# main.net
KiCad netlist of a schematic drawn in EAGLE
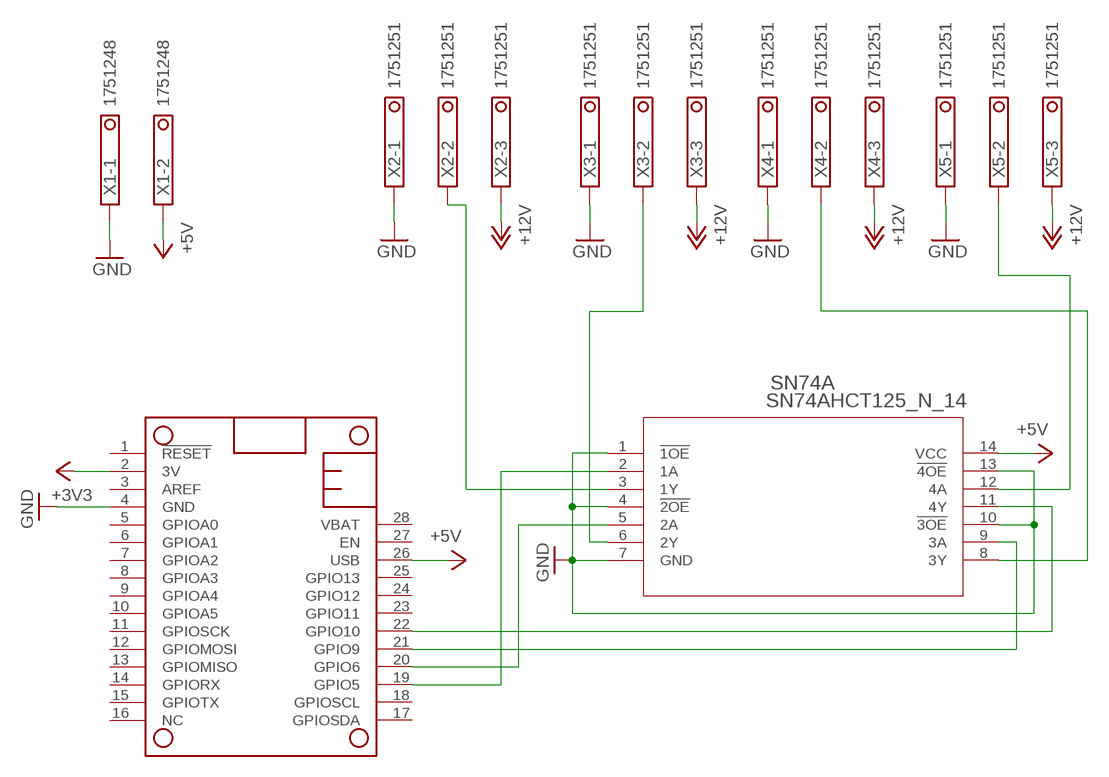
[diagram p0: schematic, sheet 1]

(export (version "E")
  (design (tool "Eeschema 10.0.6"))
  (components
    (comp (ref "MS1")
      (value "FEATHERWING_NODIM")
      (footprint "eagle-import:FEATHERWING_DIM")
      (libsource (lib "eagle-import") (part "FEATHERWING_NODIM"))
    )
    (comp (ref "SN74A")
      (value "SN74AHCT125_N_14")
      (footprint "eagle-import:N14")
      (fields (field (name "MANUFACTURER_PART_NUMBER") "sn74ahct125_n_14"))
      (libsource (lib "eagle-import") (part "SN74AHCT125_N_14"))
    )
    (comp (ref "X1")
      (value "1751248")
      (footprint "eagle-import:1751248")
      (libsource (lib "eagle-import") (part "1751248"))
    )
    (comp (ref "X2")
      (value "1751251")
      (footprint "eagle-import:1751251")
      (libsource (lib "eagle-import") (part "1751251"))
    )
    (comp (ref "X3")
      (value "1751251")
      (footprint "eagle-import:1751251")
      (libsource (lib "eagle-import") (part "1751251"))
    )
    (comp (ref "X4")
      (value "1751251")
      (footprint "eagle-import:1751251")
      (libsource (lib "eagle-import") (part "1751251"))
    )
    (comp (ref "X5")
      (value "1751251")
      (footprint "eagle-import:1751251")
      (libsource (lib "eagle-import") (part "1751251"))
    )
  )
  (nets
    (net (code "1") (name "+3V3") (class "Default")
      (node (ref "MS1") (pin "2") (pinfunction "3V_2") (pintype "power_in"))
    )
    (net (code "2") (name "+5V") (class "Default")
      (node (ref "MS1") (pin "26") (pinfunction "USB_26") (pintype "power_in"))
      (node (ref "SN74A") (pin "14") (pinfunction "VCC_14") (pintype "power_in"))
      (node (ref "X1") (pin "2") (pinfunction "K_2") (pintype "passive"))
    )
    (net (code "3") (name "+12V") (class "Default")
      (node (ref "X2") (pin "3") (pinfunction "K_3") (pintype "passive"))
      (node (ref "X3") (pin "3") (pinfunction "K_3") (pintype "passive"))
      (node (ref "X4") (pin "3") (pinfunction "K_3") (pintype "passive"))
      (node (ref "X5") (pin "3") (pinfunction "K_3") (pintype "passive"))
    )
    (net (code "4") (name "/VBAT") (class "Default")
      (node (ref "MS1") (pin "28") (pinfunction "VBAT_28") (pintype "power_in"))
    )
    (net (code "5") (name "GND") (class "Default")
      (node (ref "MS1") (pin "4") (pinfunction "GND_4") (pintype "power_in"))
      (node (ref "SN74A") (pin "1") (pinfunction "~{1OE}_1") (pintype "input"))
      (node (ref "SN74A") (pin "10") (pinfunction "~{3OE}_10") (pintype "input"))
      (node (ref "SN74A") (pin "13") (pinfunction "~{4OE}_13") (pintype "input"))
      (node (ref "SN74A") (pin "4") (pinfunction "~{2OE}_4") (pintype "input"))
      (node (ref "SN74A") (pin "7") (pinfunction "GND_7") (pintype "power_in"))
      (node (ref "X1") (pin "1") (pinfunction "K_1") (pintype "passive"))
      (node (ref "X2") (pin "1") (pinfunction "K_1") (pintype "passive"))
      (node (ref "X3") (pin "1") (pinfunction "K_1") (pintype "passive"))
      (node (ref "X4") (pin "1") (pinfunction "K_1") (pintype "passive"))
      (node (ref "X5") (pin "1") (pinfunction "K_1") (pintype "passive"))
    )
    (net (code "6") (name "Net-(MS1-GPIO5)") (class "Default")
      (node (ref "MS1") (pin "19") (pinfunction "GPIO5_19") (pintype "bidirectional"))
      (node (ref "SN74A") (pin "2") (pinfunction "1A_2") (pintype "input"))
    )
    (net (code "7") (name "Net-(MS1-GPIO6)") (class "Default")
      (node (ref "MS1") (pin "20") (pinfunction "GPIO6_20") (pintype "bidirectional"))
      (node (ref "SN74A") (pin "5") (pinfunction "2A_5") (pintype "input"))
    )
    (net (code "8") (name "Net-(MS1-GPIO9)") (class "Default")
      (node (ref "MS1") (pin "21") (pinfunction "GPIO9_21") (pintype "bidirectional"))
      (node (ref "SN74A") (pin "9") (pinfunction "3A_9") (pintype "input"))
    )
    (net (code "9") (name "Net-(MS1-GPIO10)") (class "Default")
      (node (ref "MS1") (pin "22") (pinfunction "GPIO10_22") (pintype "bidirectional"))
      (node (ref "SN74A") (pin "11") (pinfunction "4Y_11") (pintype "passive"))
    )
    (net (code "10") (name "Net-(SN74A-1Y)") (class "Default")
      (node (ref "SN74A") (pin "3") (pinfunction "1Y_3") (pintype "passive"))
      (node (ref "X2") (pin "2") (pinfunction "K_2") (pintype "passive"))
    )
    (net (code "11") (name "Net-(SN74A-2Y)") (class "Default")
      (node (ref "SN74A") (pin "6") (pinfunction "2Y_6") (pintype "passive"))
      (node (ref "X3") (pin "2") (pinfunction "K_2") (pintype "passive"))
    )
    (net (code "12") (name "Net-(SN74A-3Y)") (class "Default")
      (node (ref "SN74A") (pin "8") (pinfunction "3Y_8") (pintype "passive"))
      (node (ref "X4") (pin "2") (pinfunction "K_2") (pintype "passive"))
    )
    (net (code "13") (name "Net-(SN74A-4A)") (class "Default")
      (node (ref "SN74A") (pin "12") (pinfunction "4A_12") (pintype "input"))
      (node (ref "X5") (pin "2") (pinfunction "K_2") (pintype "passive"))
    )
    (net (code "14") (name "unconnected-(MS1-AREF-Pad3)") (class "Default")
      (node (ref "MS1") (pin "3") (pinfunction "AREF_3") (pintype "passive"))
    )
    (net (code "15") (name "unconnected-(MS1-EN-Pad27)") (class "Default")
      (node (ref "MS1") (pin "27") (pinfunction "EN_27") (pintype "passive"))
    )
    (net (code "16") (name "unconnected-(MS1-GPIO11-Pad23)") (class "Default")
      (node (ref "MS1") (pin "23") (pinfunction "GPIO11_23") (pintype "bidirectional"))
    )
    (net (code "17") (name "unconnected-(MS1-GPIO12-Pad24)") (class "Default")
      (node (ref "MS1") (pin "24") (pinfunction "GPIO12_24") (pintype "bidirectional"))
    )
    (net (code "18") (name "unconnected-(MS1-GPIO13-Pad25)") (class "Default")
      (node (ref "MS1") (pin "25") (pinfunction "GPIO13_25") (pintype "bidirectional"))
    )
    (net (code "19") (name "unconnected-(MS1-GPIOA0-Pad5)") (class "Default")
      (node (ref "MS1") (pin "5") (pinfunction "GPIOA0_5") (pintype "bidirectional"))
    )
    (net (code "20") (name "unconnected-(MS1-GPIOA1-Pad6)") (class "Default")
      (node (ref "MS1") (pin "6") (pinfunction "GPIOA1_6") (pintype "bidirectional"))
    )
    (net (code "21") (name "unconnected-(MS1-GPIOA2-Pad7)") (class "Default")
      (node (ref "MS1") (pin "7") (pinfunction "GPIOA2_7") (pintype "bidirectional"))
    )
    (net (code "22") (name "unconnected-(MS1-GPIOA3-Pad8)") (class "Default")
      (node (ref "MS1") (pin "8") (pinfunction "GPIOA3_8") (pintype "bidirectional"))
    )
    (net (code "23") (name "unconnected-(MS1-GPIOA4-Pad9)") (class "Default")
      (node (ref "MS1") (pin "9") (pinfunction "GPIOA4_9") (pintype "bidirectional"))
    )
    (net (code "24") (name "unconnected-(MS1-GPIOA5-Pad10)") (class "Default")
      (node (ref "MS1") (pin "10") (pinfunction "GPIOA5_10") (pintype "bidirectional"))
    )
    (net (code "25") (name "unconnected-(MS1-GPIOMISO-Pad13)") (class "Default")
      (node (ref "MS1") (pin "13") (pinfunction "GPIOMISO_13") (pintype "bidirectional"))
    )
    (net (code "26") (name "unconnected-(MS1-GPIOMOSI-Pad12)") (class "Default")
      (node (ref "MS1") (pin "12") (pinfunction "GPIOMOSI_12") (pintype "bidirectional"))
    )
    (net (code "27") (name "unconnected-(MS1-GPIORX-Pad14)") (class "Default")
      (node (ref "MS1") (pin "14") (pinfunction "GPIORX_14") (pintype "bidirectional"))
    )
    (net (code "28") (name "unconnected-(MS1-GPIOSCK-Pad11)") (class "Default")
      (node (ref "MS1") (pin "11") (pinfunction "GPIOSCK_11") (pintype "bidirectional"))
    )
    (net (code "29") (name "unconnected-(MS1-GPIOSCL-Pad18)") (class "Default")
      (node (ref "MS1") (pin "18") (pinfunction "GPIOSCL_18") (pintype "bidirectional"))
    )
    (net (code "30") (name "unconnected-(MS1-GPIOSDA-Pad17)") (class "Default")
      (node (ref "MS1") (pin "17") (pinfunction "GPIOSDA_17") (pintype "bidirectional"))
    )
    (net (code "31") (name "unconnected-(MS1-GPIOTX-Pad15)") (class "Default")
      (node (ref "MS1") (pin "15") (pinfunction "GPIOTX_15") (pintype "bidirectional"))
    )
    (net (code "32") (name "unconnected-(MS1-NC-Pad16)") (class "Default")
      (node (ref "MS1") (pin "16") (pinfunction "NC_16") (pintype "passive"))
    )
    (net (code "33") (name "unconnected-(MS1-~{RESET}-Pad1)") (class "Default")
      (node (ref "MS1") (pin "1") (pinfunction "~{RESET}_1") (pintype "input"))
    )
  )
)
